# esp8266.net
KiCad netlist of a schematic drawn in EAGLE
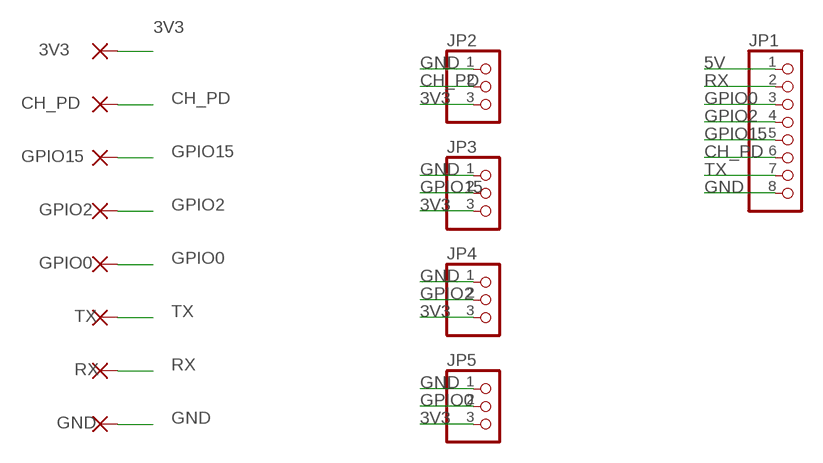
[diagram p0: schematic, sheet 1]

(export (version "E")
  (design (tool "Eeschema 10.0.6"))
  (components
    (comp (ref "3V3")
      (value "1,6/0,9")
      (footprint "eagle-import:1,6_0,9")
      (libsource (lib "eagle-import") (part "1,6/0,9"))
    )
    (comp (ref "CH_PD")
      (value "1,6/0,9")
      (footprint "eagle-import:1,6_0,9")
      (libsource (lib "eagle-import") (part "1,6/0,9"))
    )
    (comp (ref "GND")
      (value "1,6/0,9")
      (footprint "eagle-import:1,6_0,9")
      (libsource (lib "eagle-import") (part "1,6/0,9"))
    )
    (comp (ref "GPIO0")
      (value "1,6/0,9")
      (footprint "eagle-import:1,6_0,9")
      (libsource (lib "eagle-import") (part "1,6/0,9"))
    )
    (comp (ref "GPIO2")
      (value "1,6/0,9")
      (footprint "eagle-import:1,6_0,9")
      (libsource (lib "eagle-import") (part "1,6/0,9"))
    )
    (comp (ref "GPIO15")
      (value "1,6/0,9")
      (footprint "eagle-import:1,6_0,9")
      (libsource (lib "eagle-import") (part "1,6/0,9"))
    )
    (comp (ref "JP1")
      (value "PINHD-1X8")
      (footprint "eagle-import:1X08")
      (libsource (lib "eagle-import") (part "PINHD-1X8"))
    )
    (comp (ref "JP2")
      (value "PINHD-1X3")
      (footprint "eagle-import:1X03")
      (libsource (lib "eagle-import") (part "PINHD-1X3"))
    )
    (comp (ref "JP3")
      (value "PINHD-1X3")
      (footprint "eagle-import:1X03")
      (libsource (lib "eagle-import") (part "PINHD-1X3"))
    )
    (comp (ref "JP4")
      (value "PINHD-1X3")
      (footprint "eagle-import:1X03")
      (libsource (lib "eagle-import") (part "PINHD-1X3"))
    )
    (comp (ref "JP5")
      (value "PINHD-1X3")
      (footprint "eagle-import:1X03")
      (libsource (lib "eagle-import") (part "PINHD-1X3"))
    )
    (comp (ref "RX")
      (value "1,6/0,9")
      (footprint "eagle-import:1,6_0,9")
      (libsource (lib "eagle-import") (part "1,6/0,9"))
    )
    (comp (ref "TX")
      (value "1,6/0,9")
      (footprint "eagle-import:1,6_0,9")
      (libsource (lib "eagle-import") (part "1,6/0,9"))
    )
  )
  (nets
    (net (code "1") (name "/3V3") (class "Default")
      (node (ref "3V3") (pin "1") (pinfunction "P_1") (pintype "passive"))
      (node (ref "JP2") (pin "3") (pinfunction "3_3") (pintype "passive"))
      (node (ref "JP3") (pin "3") (pinfunction "3_3") (pintype "passive"))
      (node (ref "JP4") (pin "3") (pinfunction "3_3") (pintype "passive"))
      (node (ref "JP5") (pin "3") (pinfunction "3_3") (pintype "passive"))
    )
    (net (code "2") (name "/5V") (class "Default")
      (node (ref "JP1") (pin "1") (pinfunction "1_1") (pintype "passive"))
    )
    (net (code "3") (name "/CH_PD") (class "Default")
      (node (ref "CH_PD") (pin "1") (pinfunction "P_1") (pintype "passive"))
      (node (ref "JP1") (pin "6") (pinfunction "6_6") (pintype "passive"))
      (node (ref "JP2") (pin "2") (pinfunction "2_2") (pintype "passive"))
    )
    (net (code "4") (name "/GND") (class "Default")
      (node (ref "GND") (pin "1") (pinfunction "P_1") (pintype "passive"))
      (node (ref "JP1") (pin "8") (pinfunction "8_8") (pintype "passive"))
      (node (ref "JP2") (pin "1") (pinfunction "1_1") (pintype "passive"))
      (node (ref "JP3") (pin "1") (pinfunction "1_1") (pintype "passive"))
      (node (ref "JP4") (pin "1") (pinfunction "1_1") (pintype "passive"))
      (node (ref "JP5") (pin "1") (pinfunction "1_1") (pintype "passive"))
    )
    (net (code "5") (name "/GPIO0") (class "Default")
      (node (ref "GPIO0") (pin "1") (pinfunction "P_1") (pintype "passive"))
      (node (ref "JP1") (pin "3") (pinfunction "3_3") (pintype "passive"))
      (node (ref "JP5") (pin "2") (pinfunction "2_2") (pintype "passive"))
    )
    (net (code "6") (name "/GPIO2") (class "Default")
      (node (ref "GPIO2") (pin "1") (pinfunction "P_1") (pintype "passive"))
      (node (ref "JP1") (pin "4") (pinfunction "4_4") (pintype "passive"))
      (node (ref "JP4") (pin "2") (pinfunction "2_2") (pintype "passive"))
    )
    (net (code "7") (name "/GPIO15") (class "Default")
      (node (ref "GPIO15") (pin "1") (pinfunction "P_1") (pintype "passive"))
      (node (ref "JP1") (pin "5") (pinfunction "5_5") (pintype "passive"))
      (node (ref "JP3") (pin "2") (pinfunction "2_2") (pintype "passive"))
    )
    (net (code "8") (name "/RX") (class "Default")
      (node (ref "JP1") (pin "2") (pinfunction "2_2") (pintype "passive"))
      (node (ref "RX") (pin "1") (pinfunction "P_1") (pintype "passive"))
    )
    (net (code "9") (name "/TX") (class "Default")
      (node (ref "JP1") (pin "7") (pinfunction "7_7") (pintype "passive"))
      (node (ref "TX") (pin "1") (pinfunction "P_1") (pintype "passive"))
    )
  )
)
